# Dario_-_Rev_A1.net
KiCad netlist of a schematic drawn in EAGLE
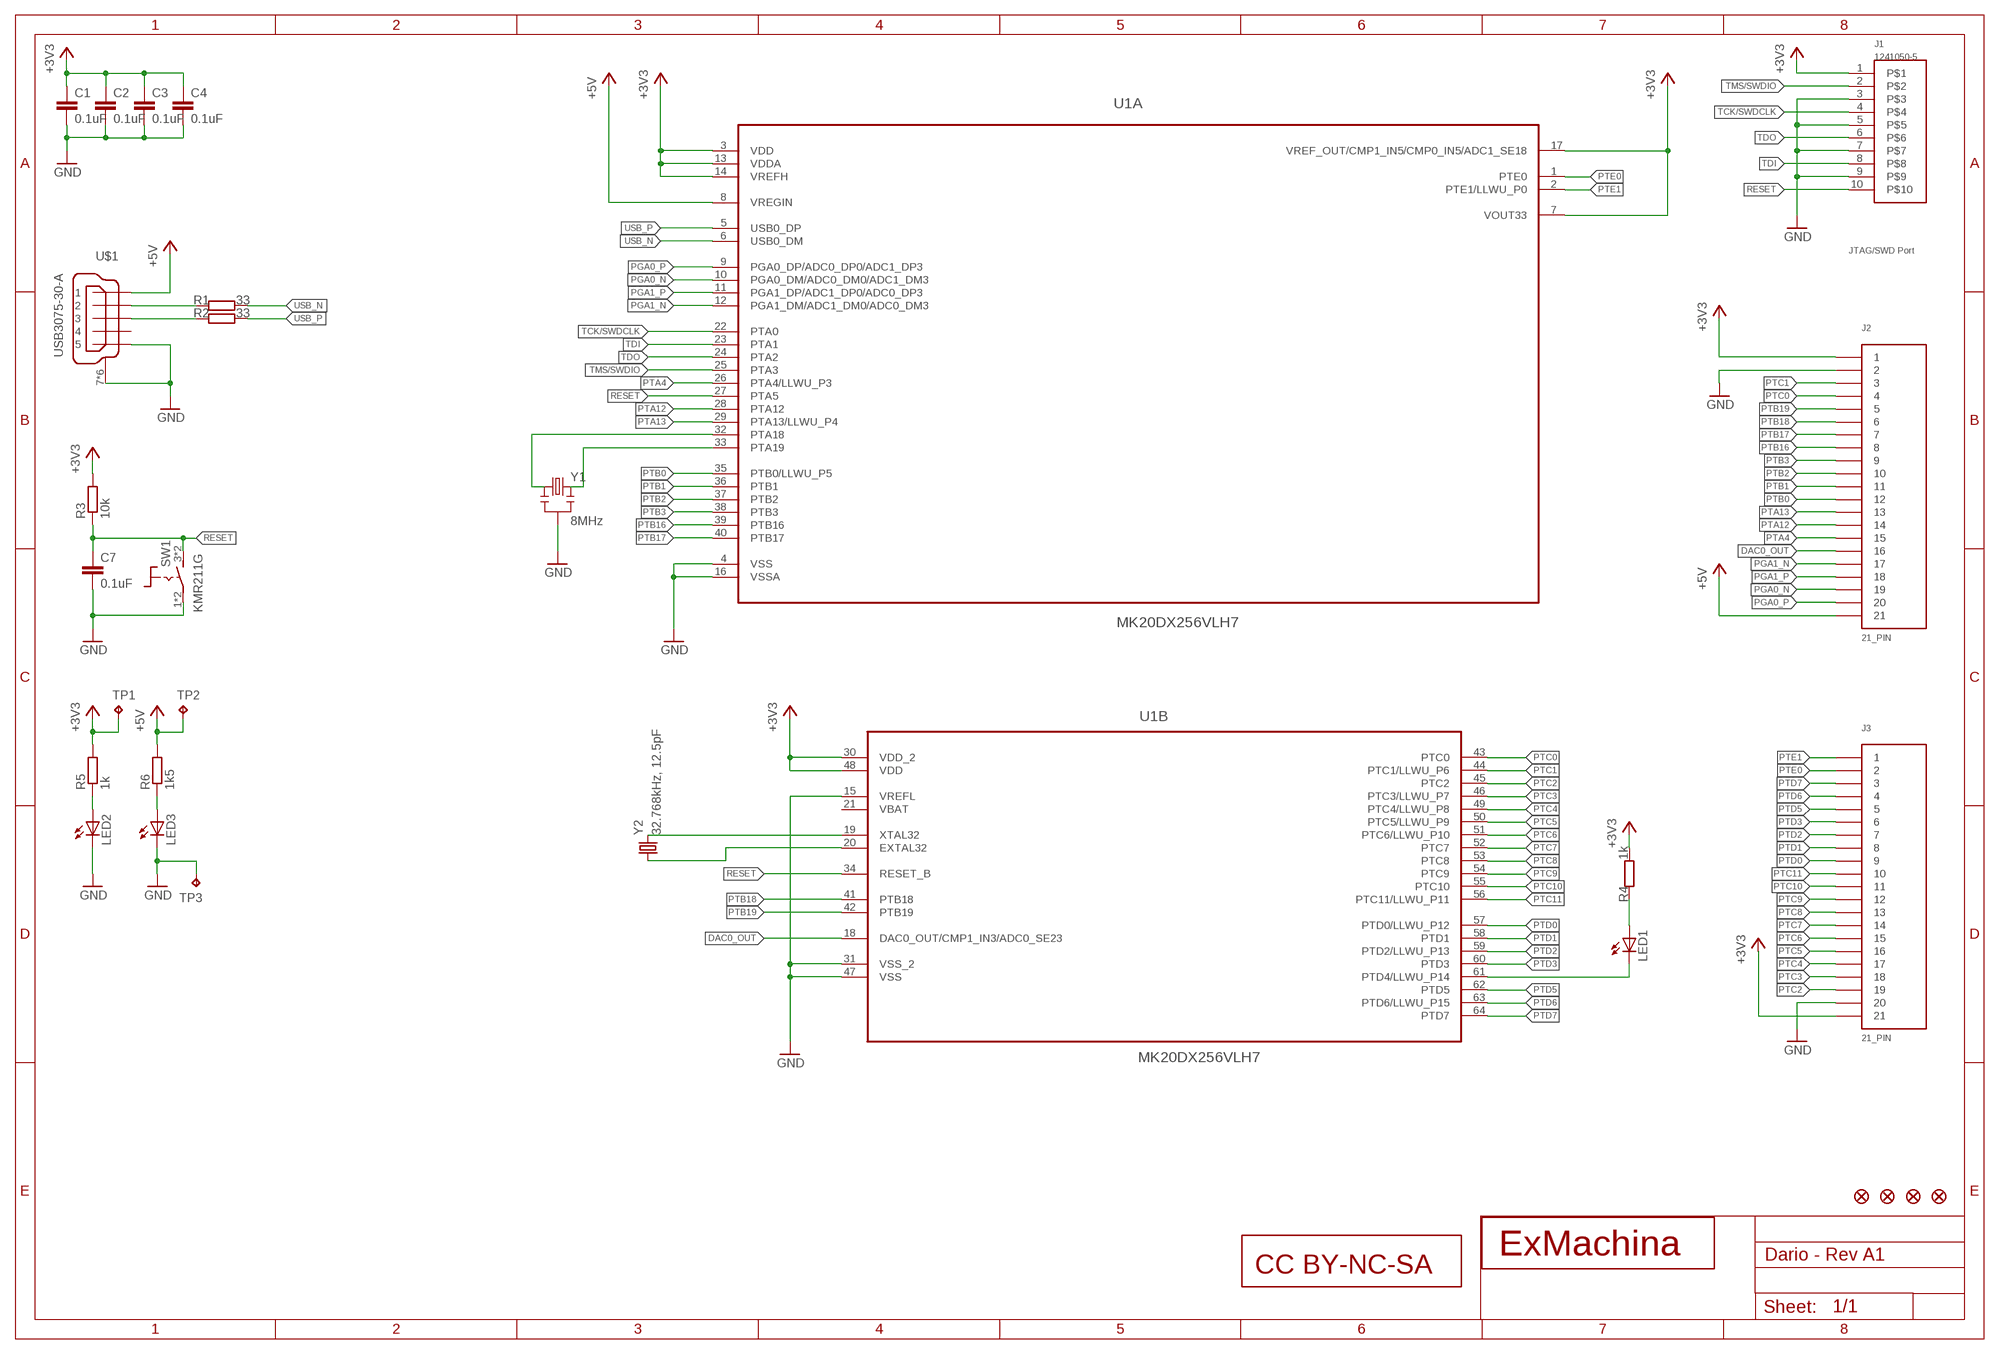
[diagram p0: schematic, sheet 1]

(export (version "E")
  (design (tool "Eeschema 10.0.6"))
  (components
    (comp (ref "C1")
      (value "0.1uF")
      (footprint "eagle-import:C0603")
      (fields (field (name "MPN") "MC0603B104K160CT"))
      (libsource (lib "eagle-import") (part "C-EUC0603"))
    )
    (comp (ref "C2")
      (value "0.1uF")
      (footprint "eagle-import:C0603")
      (fields (field (name "MPN") "MC0603B104K160CT"))
      (libsource (lib "eagle-import") (part "C-EUC0603"))
    )
    (comp (ref "C3")
      (value "0.1uF")
      (footprint "eagle-import:C0603")
      (fields (field (name "MPN") "MC0603B104K160CT"))
      (libsource (lib "eagle-import") (part "C-EUC0603"))
    )
    (comp (ref "C4")
      (value "0.1uF")
      (footprint "eagle-import:C0603")
      (fields (field (name "MPN") "MC0603B104K160CT"))
      (libsource (lib "eagle-import") (part "C-EUC0603"))
    )
    (comp (ref "C7")
      (value "0.1uF")
      (footprint "eagle-import:C0603")
      (fields (field (name "MPN") "MC0603B104K160CT"))
      (libsource (lib "eagle-import") (part "C-EUC0603"))
    )
    (comp (ref "J1")
      (value "1241050-5")
      (footprint "eagle-import:2.54_2X5")
      (libsource (lib "eagle-import") (part "1241050-5"))
    )
    (comp (ref "J2")
      (value "21_PIN")
      (footprint "eagle-import:21_CUSTOM")
      (libsource (lib "eagle-import") (part "21_PIN"))
    )
    (comp (ref "J3")
      (value "21_PIN")
      (footprint "eagle-import:21_CUSTOM")
      (libsource (lib "eagle-import") (part "21_PIN"))
    )
    (comp (ref "JP1")
      (value "FIDUCIAL1X2")
      (footprint "eagle-import:FIDUCIAL-1X2")
      (libsource (lib "eagle-import") (part "FIDUCIAL1X2"))
    )
    (comp (ref "JP2")
      (value "FIDUCIAL1X2")
      (footprint "eagle-import:FIDUCIAL-1X2")
      (libsource (lib "eagle-import") (part "FIDUCIAL1X2"))
    )
    (comp (ref "JP3")
      (value "FIDUCIAL1X2")
      (footprint "eagle-import:FIDUCIAL-1X2")
      (libsource (lib "eagle-import") (part "FIDUCIAL1X2"))
    )
    (comp (ref "JP4")
      (value "FIDUCIAL1X2")
      (footprint "eagle-import:FIDUCIAL-1X2")
      (libsource (lib "eagle-import") (part "FIDUCIAL1X2"))
    )
    (comp (ref "LED1")
      (value "LEDCHIP-LED0603")
      (footprint "eagle-import:CHIP-LED0603")
      (libsource (lib "eagle-import") (part "LEDCHIP-LED0603"))
    )
    (comp (ref "LED2")
      (value "LEDCHIP-LED0603")
      (footprint "eagle-import:CHIP-LED0603")
      (libsource (lib "eagle-import") (part "LEDCHIP-LED0603"))
    )
    (comp (ref "LED3")
      (value "LEDCHIP-LED0603")
      (footprint "eagle-import:CHIP-LED0603")
      (libsource (lib "eagle-import") (part "LEDCHIP-LED0603"))
    )
    (comp (ref "R1")
      (value "33")
      (footprint "eagle-import:R0603")
      (fields (field (name "MPN") "MCMR06X33R0FTL"))
      (libsource (lib "eagle-import") (part "R-EU_R0603"))
    )
    (comp (ref "R2")
      (value "33")
      (footprint "eagle-import:R0603")
      (fields (field (name "MPN") "MCMR06X33R0FTL"))
      (libsource (lib "eagle-import") (part "R-EU_R0603"))
    )
    (comp (ref "R3")
      (value "10k")
      (footprint "eagle-import:R0603")
      (fields (field (name "MPN") "MCMR06X1002FTL"))
      (libsource (lib "eagle-import") (part "R-EU_R0603"))
    )
    (comp (ref "R4")
      (value "1k")
      (footprint "eagle-import:R0603")
      (fields (field (name "MPN") "MCMR06X1001FTL"))
      (libsource (lib "eagle-import") (part "R-EU_R0603"))
    )
    (comp (ref "R5")
      (value "1k")
      (footprint "eagle-import:R0603")
      (fields (field (name "MPN") "MCMR06X1001FTL"))
      (libsource (lib "eagle-import") (part "R-EU_R0603"))
    )
    (comp (ref "R6")
      (value "1k5")
      (footprint "eagle-import:R0603")
      (fields (field (name "MPN") "MCMR06X1501FTL"))
      (libsource (lib "eagle-import") (part "R-EU_R0603"))
    )
    (comp (ref "SW1")
      (value "KMR211G")
      (footprint "eagle-import:KM_SERIE")
      (fields (field (name "MPN") "KMR211G LFS"))
      (libsource (lib "eagle-import") (part "KMR211G"))
    )
    (comp (ref "TP1")
      (value "TPB1,27")
      (footprint "eagle-import:B1,27")
      (libsource (lib "eagle-import") (part "TPB1,27"))
    )
    (comp (ref "TP2")
      (value "TPB1,27")
      (footprint "eagle-import:B1,27")
      (libsource (lib "eagle-import") (part "TPB1,27"))
    )
    (comp (ref "TP3")
      (value "TPB1,27")
      (footprint "eagle-import:B1,27")
      (libsource (lib "eagle-import") (part "TPB1,27"))
    )
    (comp (ref "U$1")
      (value "USB3075-30-A")
      (footprint "eagle-import:USB_MICROB_SMT")
      (libsource (lib "eagle-import") (part "USB3075-30-A"))
    )
    (comp (ref "U$3")
      (value "EXMACHINA-LOGO-NAME")
      (footprint "eagle-import:EXM-LOGO-BASELINE")
      (libsource (lib "eagle-import") (part "EXMACHINA-LOGO-NAME"))
    )
    (comp (ref "U$4")
      (value "CC-BY-NC-SA")
      (footprint "eagle-import:CC-BY-NC-SA")
      (libsource (lib "eagle-import") (part "CC-BY-NC-SA"))
    )
    (comp (ref "U1")
      (value "MK20DX256VLH7")
      (footprint "eagle-import:QFP50P1200X1200X160-64N")
      (libsource (lib "eagle-import") (part "MK20DX256VLH7"))
    )
    (comp (ref "Y1")
      (value "8MHz")
      (footprint "eagle-import:RESONATOR-SMD")
      (fields (field (name "MPN") "CSTCE8M00G55Z-R0"))
      (libsource (lib "eagle-import") (part "RESONATORSMD"))
    )
    (comp (ref "Y2")
      (value "32.768kHz, 12.5pF")
      (footprint "eagle-import:ABS07")
      (fields (field (name "MPN") "ABS07-32.768KHZ-1-T"))
      (libsource (lib "eagle-import") (part "ABS07-?32.768KHZ"))
    )
  )
  (nets
    (net (code "1") (name "+3V3") (class "Default")
      (node (ref "C1") (pin "1") (pinfunction "1_1") (pintype "passive"))
      (node (ref "C2") (pin "1") (pinfunction "1_1") (pintype "passive"))
      (node (ref "C3") (pin "1") (pinfunction "1_1") (pintype "passive"))
      (node (ref "C4") (pin "1") (pinfunction "1_1") (pintype "passive"))
      (node (ref "J1") (pin "1") (pinfunction "P$1_1") (pintype "bidirectional"))
      (node (ref "J2") (pin "P$1") (pinfunction "1_P$1") (pintype "bidirectional"))
      (node (ref "J3") (pin "P$21") (pinfunction "21_P$21") (pintype "bidirectional"))
      (node (ref "R3") (pin "2") (pinfunction "2_2") (pintype "passive"))
      (node (ref "R4") (pin "2") (pinfunction "2_2") (pintype "passive"))
      (node (ref "R5") (pin "2") (pinfunction "2_2") (pintype "passive"))
      (node (ref "TP1") (pin "TP") (pinfunction "TP_TP") (pintype "input"))
      (node (ref "U1") (pin "13") (pinfunction "VDDA_13") (pintype "power_in"))
      (node (ref "U1") (pin "14") (pinfunction "VREFH_14") (pintype "passive"))
      (node (ref "U1") (pin "17") (pinfunction "VREF_OUT/CMP1_IN5/CMP0_IN5/ADC1_SE18_17") (pintype "output"))
      (node (ref "U1") (pin "3") (pinfunction "VDD_3") (pintype "power_in"))
      (node (ref "U1") (pin "30") (pinfunction "VDD_2_30") (pintype "power_in"))
      (node (ref "U1") (pin "48") (pinfunction "VDD_48") (pintype "power_in"))
      (node (ref "U1") (pin "7") (pinfunction "VOUT33_7") (pintype "output"))
    )
    (net (code "2") (name "+5V") (class "Default")
      (node (ref "J2") (pin "P$21") (pinfunction "21_P$21") (pintype "bidirectional"))
      (node (ref "R6") (pin "2") (pinfunction "2_2") (pintype "passive"))
      (node (ref "TP2") (pin "TP") (pinfunction "TP_TP") (pintype "input"))
      (node (ref "U$1") (pin "1") (pinfunction "1_1") (pintype "passive"))
      (node (ref "U1") (pin "8") (pinfunction "VREGIN_8") (pintype "input"))
    )
    (net (code "3") (name "/VBAT") (class "Default")
      (node (ref "U1") (pin "21") (pinfunction "VBAT_21") (pintype "power_in"))
    )
    (net (code "4") (name "DAC0_OUT") (class "Default")
      (node (ref "J2") (pin "P$16") (pinfunction "16_P$16") (pintype "bidirectional"))
      (node (ref "U1") (pin "18") (pinfunction "DAC0_OUT/CMP1_IN3/ADC0_SE23_18") (pintype "passive"))
    )
    (net (code "5") (name "GND") (class "Default")
      (node (ref "C1") (pin "2") (pinfunction "2_2") (pintype "passive"))
      (node (ref "C2") (pin "2") (pinfunction "2_2") (pintype "passive"))
      (node (ref "C3") (pin "2") (pinfunction "2_2") (pintype "passive"))
      (node (ref "C4") (pin "2") (pinfunction "2_2") (pintype "passive"))
      (node (ref "C7") (pin "2") (pinfunction "2_2") (pintype "passive"))
      (node (ref "J1") (pin "3") (pinfunction "P$3_3") (pintype "bidirectional"))
      (node (ref "J1") (pin "5") (pinfunction "P$5_5") (pintype "bidirectional"))
      (node (ref "J1") (pin "7") (pinfunction "P$7_7") (pintype "bidirectional"))
      (node (ref "J1") (pin "9") (pinfunction "P$9_9") (pintype "bidirectional"))
      (node (ref "J2") (pin "P$2") (pinfunction "2_P$2") (pintype "bidirectional"))
      (node (ref "J3") (pin "P$20") (pinfunction "20_P$20") (pintype "bidirectional"))
      (node (ref "LED2") (pin "C") (pinfunction "C_C") (pintype "passive"))
      (node (ref "LED3") (pin "C") (pinfunction "C_C") (pintype "passive"))
      (node (ref "SW1") (pin "1") (pinfunction "2_1") (pintype "passive"))
      (node (ref "SW1") (pin "2") (pinfunction "2_2") (pintype "passive"))
      (node (ref "TP3") (pin "TP") (pinfunction "TP_TP") (pintype "input"))
      (node (ref "U$1") (pin "10") (pinfunction "S_10") (pintype "bidirectional"))
      (node (ref "U$1") (pin "11") (pinfunction "S_11") (pintype "bidirectional"))
      (node (ref "U$1") (pin "12") (pinfunction "S_12") (pintype "bidirectional"))
      (node (ref "U$1") (pin "5") (pinfunction "5_5") (pintype "passive"))
      (node (ref "U$1") (pin "7") (pinfunction "S_7") (pintype "bidirectional"))
      (node (ref "U$1") (pin "8") (pinfunction "S_8") (pintype "bidirectional"))
      (node (ref "U$1") (pin "9") (pinfunction "S_9") (pintype "bidirectional"))
      (node (ref "U1") (pin "15") (pinfunction "VREFL_15") (pintype "passive"))
      (node (ref "U1") (pin "16") (pinfunction "VSSA_16") (pintype "passive"))
      (node (ref "U1") (pin "31") (pinfunction "VSS_2_31") (pintype "passive"))
      (node (ref "U1") (pin "4") (pinfunction "VSS_4") (pintype "passive"))
      (node (ref "U1") (pin "47") (pinfunction "VSS_47") (pintype "passive"))
      (node (ref "Y1") (pin "2") (pinfunction "2_2") (pintype "passive"))
    )
    (net (code "6") (name "Net-(LED1-PadA)") (class "Default")
      (node (ref "LED1") (pin "A") (pinfunction "A_A") (pintype "passive"))
      (node (ref "R4") (pin "1") (pinfunction "1_1") (pintype "passive"))
    )
    (net (code "7") (name "Net-(LED2-PadA)") (class "Default")
      (node (ref "LED2") (pin "A") (pinfunction "A_A") (pintype "passive"))
      (node (ref "R5") (pin "1") (pinfunction "1_1") (pintype "passive"))
    )
    (net (code "8") (name "Net-(LED3-PadA)") (class "Default")
      (node (ref "LED3") (pin "A") (pinfunction "A_A") (pintype "passive"))
      (node (ref "R6") (pin "1") (pinfunction "1_1") (pintype "passive"))
    )
    (net (code "9") (name "Net-(R1-Pad1)") (class "Default")
      (node (ref "R1") (pin "1") (pinfunction "1_1") (pintype "passive"))
      (node (ref "U$1") (pin "2") (pinfunction "2_2") (pintype "passive"))
    )
    (net (code "10") (name "Net-(R2-Pad1)") (class "Default")
      (node (ref "R2") (pin "1") (pinfunction "1_1") (pintype "passive"))
      (node (ref "U$1") (pin "3") (pinfunction "3_3") (pintype "passive"))
    )
    (net (code "11") (name "Net-(U1A-PTA18)") (class "Default")
      (node (ref "U1") (pin "32") (pinfunction "PTA18_32") (pintype "bidirectional"))
      (node (ref "Y1") (pin "1") (pinfunction "1_1") (pintype "passive"))
    )
    (net (code "12") (name "Net-(U1A-PTA19)") (class "Default")
      (node (ref "U1") (pin "33") (pinfunction "PTA19_33") (pintype "bidirectional"))
      (node (ref "Y1") (pin "3") (pinfunction "3_3") (pintype "passive"))
    )
    (net (code "13") (name "Net-(U1B-EXTAL32)") (class "Default")
      (node (ref "U1") (pin "20") (pinfunction "EXTAL32_20") (pintype "passive"))
      (node (ref "Y2") (pin "1") (pinfunction "1_1") (pintype "passive"))
    )
    (net (code "14") (name "Net-(U1B-PTD4{slash}LLWU_P14)") (class "Default")
      (node (ref "LED1") (pin "C") (pinfunction "C_C") (pintype "passive"))
      (node (ref "U1") (pin "61") (pinfunction "PTD4/LLWU_P14_61") (pintype "bidirectional"))
    )
    (net (code "15") (name "Net-(U1B-XTAL32)") (class "Default")
      (node (ref "U1") (pin "19") (pinfunction "XTAL32_19") (pintype "passive"))
      (node (ref "Y2") (pin "2") (pinfunction "2_2") (pintype "passive"))
    )
    (net (code "16") (name "PGA0_N") (class "Default")
      (node (ref "J2") (pin "P$19") (pinfunction "19_P$19") (pintype "bidirectional"))
      (node (ref "U1") (pin "10") (pinfunction "PGA0_DM/ADC0_DM0/ADC1_DM3_10") (pintype "bidirectional"))
    )
    (net (code "17") (name "PGA0_P") (class "Default")
      (node (ref "J2") (pin "P$20") (pinfunction "20_P$20") (pintype "bidirectional"))
      (node (ref "U1") (pin "9") (pinfunction "PGA0_DP/ADC0_DP0/ADC1_DP3_9") (pintype "bidirectional"))
    )
    (net (code "18") (name "PGA1_N") (class "Default")
      (node (ref "J2") (pin "P$17") (pinfunction "17_P$17") (pintype "bidirectional"))
      (node (ref "U1") (pin "12") (pinfunction "PGA1_DM/ADC1_DM0/ADC0_DM3_12") (pintype "bidirectional"))
    )
    (net (code "19") (name "PGA1_P") (class "Default")
      (node (ref "J2") (pin "P$18") (pinfunction "18_P$18") (pintype "bidirectional"))
      (node (ref "U1") (pin "11") (pinfunction "PGA1_DP/ADC1_DP0/ADC0_DP3_11") (pintype "bidirectional"))
    )
    (net (code "20") (name "PTA4") (class "Default")
      (node (ref "J2") (pin "P$15") (pinfunction "15_P$15") (pintype "bidirectional"))
      (node (ref "U1") (pin "26") (pinfunction "PTA4/LLWU_P3_26") (pintype "bidirectional"))
    )
    (net (code "21") (name "PTA12") (class "Default")
      (node (ref "J2") (pin "P$14") (pinfunction "14_P$14") (pintype "bidirectional"))
      (node (ref "U1") (pin "28") (pinfunction "PTA12_28") (pintype "bidirectional"))
    )
    (net (code "22") (name "PTA13") (class "Default")
      (node (ref "J2") (pin "P$13") (pinfunction "13_P$13") (pintype "bidirectional"))
      (node (ref "U1") (pin "29") (pinfunction "PTA13/LLWU_P4_29") (pintype "bidirectional"))
    )
    (net (code "23") (name "PTB0") (class "Default")
      (node (ref "J2") (pin "P$12") (pinfunction "12_P$12") (pintype "bidirectional"))
      (node (ref "U1") (pin "35") (pinfunction "PTB0/LLWU_P5_35") (pintype "bidirectional"))
    )
    (net (code "24") (name "PTB1") (class "Default")
      (node (ref "J2") (pin "P$11") (pinfunction "11_P$11") (pintype "bidirectional"))
      (node (ref "U1") (pin "36") (pinfunction "PTB1_36") (pintype "bidirectional"))
    )
    (net (code "25") (name "PTB2") (class "Default")
      (node (ref "J2") (pin "P$10") (pinfunction "10_P$10") (pintype "bidirectional"))
      (node (ref "U1") (pin "37") (pinfunction "PTB2_37") (pintype "bidirectional"))
    )
    (net (code "26") (name "PTB3") (class "Default")
      (node (ref "J2") (pin "P$9") (pinfunction "9_P$9") (pintype "bidirectional"))
      (node (ref "U1") (pin "38") (pinfunction "PTB3_38") (pintype "bidirectional"))
    )
    (net (code "27") (name "PTB16") (class "Default")
      (node (ref "J2") (pin "P$8") (pinfunction "8_P$8") (pintype "bidirectional"))
      (node (ref "U1") (pin "39") (pinfunction "PTB16_39") (pintype "bidirectional"))
    )
    (net (code "28") (name "PTB17") (class "Default")
      (node (ref "J2") (pin "P$7") (pinfunction "7_P$7") (pintype "bidirectional"))
      (node (ref "U1") (pin "40") (pinfunction "PTB17_40") (pintype "bidirectional"))
    )
    (net (code "29") (name "PTB18") (class "Default")
      (node (ref "J2") (pin "P$6") (pinfunction "6_P$6") (pintype "bidirectional"))
      (node (ref "U1") (pin "41") (pinfunction "PTB18_41") (pintype "bidirectional"))
    )
    (net (code "30") (name "PTB19") (class "Default")
      (node (ref "J2") (pin "P$5") (pinfunction "5_P$5") (pintype "bidirectional"))
      (node (ref "U1") (pin "42") (pinfunction "PTB19_42") (pintype "bidirectional"))
    )
    (net (code "31") (name "PTC0") (class "Default")
      (node (ref "J2") (pin "P$4") (pinfunction "4_P$4") (pintype "bidirectional"))
      (node (ref "U1") (pin "43") (pinfunction "PTC0_43") (pintype "bidirectional"))
    )
    (net (code "32") (name "PTC1") (class "Default")
      (node (ref "J2") (pin "P$3") (pinfunction "3_P$3") (pintype "bidirectional"))
      (node (ref "U1") (pin "44") (pinfunction "PTC1/LLWU_P6_44") (pintype "bidirectional"))
    )
    (net (code "33") (name "PTC2") (class "Default")
      (node (ref "J3") (pin "P$19") (pinfunction "19_P$19") (pintype "bidirectional"))
      (node (ref "U1") (pin "45") (pinfunction "PTC2_45") (pintype "bidirectional"))
    )
    (net (code "34") (name "PTC3") (class "Default")
      (node (ref "J3") (pin "P$18") (pinfunction "18_P$18") (pintype "bidirectional"))
      (node (ref "U1") (pin "46") (pinfunction "PTC3/LLWU_P7_46") (pintype "bidirectional"))
    )
    (net (code "35") (name "PTC4") (class "Default")
      (node (ref "J3") (pin "P$17") (pinfunction "17_P$17") (pintype "bidirectional"))
      (node (ref "U1") (pin "49") (pinfunction "PTC4/LLWU_P8_49") (pintype "bidirectional"))
    )
    (net (code "36") (name "PTC5") (class "Default")
      (node (ref "J3") (pin "P$16") (pinfunction "16_P$16") (pintype "bidirectional"))
      (node (ref "U1") (pin "50") (pinfunction "PTC5/LLWU_P9_50") (pintype "bidirectional"))
    )
    (net (code "37") (name "PTC6") (class "Default")
      (node (ref "J3") (pin "P$15") (pinfunction "15_P$15") (pintype "bidirectional"))
      (node (ref "U1") (pin "51") (pinfunction "PTC6/LLWU_P10_51") (pintype "bidirectional"))
    )
    (net (code "38") (name "PTC7") (class "Default")
      (node (ref "J3") (pin "P$14") (pinfunction "14_P$14") (pintype "bidirectional"))
      (node (ref "U1") (pin "52") (pinfunction "PTC7_52") (pintype "bidirectional"))
    )
    (net (code "39") (name "PTC8") (class "Default")
      (node (ref "J3") (pin "P$13") (pinfunction "13_P$13") (pintype "bidirectional"))
      (node (ref "U1") (pin "53") (pinfunction "PTC8_53") (pintype "bidirectional"))
    )
    (net (code "40") (name "PTC9") (class "Default")
      (node (ref "J3") (pin "P$12") (pinfunction "12_P$12") (pintype "bidirectional"))
      (node (ref "U1") (pin "54") (pinfunction "PTC9_54") (pintype "bidirectional"))
    )
    (net (code "41") (name "PTC10") (class "Default")
      (node (ref "J3") (pin "P$11") (pinfunction "11_P$11") (pintype "bidirectional"))
      (node (ref "U1") (pin "55") (pinfunction "PTC10_55") (pintype "bidirectional"))
    )
    (net (code "42") (name "PTC11") (class "Default")
      (node (ref "J3") (pin "P$10") (pinfunction "10_P$10") (pintype "bidirectional"))
      (node (ref "U1") (pin "56") (pinfunction "PTC11/LLWU_P11_56") (pintype "bidirectional"))
    )
    (net (code "43") (name "PTD0") (class "Default")
      (node (ref "J3") (pin "P$9") (pinfunction "9_P$9") (pintype "bidirectional"))
      (node (ref "U1") (pin "57") (pinfunction "PTD0/LLWU_P12_57") (pintype "bidirectional"))
    )
    (net (code "44") (name "PTD1") (class "Default")
      (node (ref "J3") (pin "P$8") (pinfunction "8_P$8") (pintype "bidirectional"))
      (node (ref "U1") (pin "58") (pinfunction "PTD1_58") (pintype "bidirectional"))
    )
    (net (code "45") (name "PTD2") (class "Default")
      (node (ref "J3") (pin "P$7") (pinfunction "7_P$7") (pintype "bidirectional"))
      (node (ref "U1") (pin "59") (pinfunction "PTD2/LLWU_P13_59") (pintype "bidirectional"))
    )
    (net (code "46") (name "PTD3") (class "Default")
      (node (ref "J3") (pin "P$6") (pinfunction "6_P$6") (pintype "bidirectional"))
      (node (ref "U1") (pin "60") (pinfunction "PTD3_60") (pintype "bidirectional"))
    )
    (net (code "47") (name "PTD5") (class "Default")
      (node (ref "J3") (pin "P$5") (pinfunction "5_P$5") (pintype "bidirectional"))
      (node (ref "U1") (pin "62") (pinfunction "PTD5_62") (pintype "bidirectional"))
    )
    (net (code "48") (name "PTD6") (class "Default")
      (node (ref "J3") (pin "P$4") (pinfunction "4_P$4") (pintype "bidirectional"))
      (node (ref "U1") (pin "63") (pinfunction "PTD6/LLWU_P15_63") (pintype "bidirectional"))
    )
    (net (code "49") (name "PTD7") (class "Default")
      (node (ref "J3") (pin "P$3") (pinfunction "3_P$3") (pintype "bidirectional"))
      (node (ref "U1") (pin "64") (pinfunction "PTD7_64") (pintype "bidirectional"))
    )
    (net (code "50") (name "PTE0") (class "Default")
      (node (ref "J3") (pin "P$2") (pinfunction "2_P$2") (pintype "bidirectional"))
      (node (ref "U1") (pin "1") (pinfunction "PTE0_1") (pintype "bidirectional"))
    )
    (net (code "51") (name "PTE1") (class "Default")
      (node (ref "J3") (pin "P$1") (pinfunction "1_P$1") (pintype "bidirectional"))
      (node (ref "U1") (pin "2") (pinfunction "PTE1/LLWU_P0_2") (pintype "bidirectional"))
    )
    (net (code "52") (name "RESET") (class "Default")
      (node (ref "C7") (pin "1") (pinfunction "1_1") (pintype "passive"))
      (node (ref "J1") (pin "10") (pinfunction "P$10_10") (pintype "bidirectional"))
      (node (ref "R3") (pin "1") (pinfunction "1_1") (pintype "passive"))
      (node (ref "SW1") (pin "3") (pinfunction "1_3") (pintype "passive"))
      (node (ref "SW1") (pin "4") (pinfunction "1_4") (pintype "passive"))
      (node (ref "U1") (pin "27") (pinfunction "PTA5_27") (pintype "bidirectional"))
      (node (ref "U1") (pin "34") (pinfunction "RESET_B_34") (pintype "passive"))
    )
    (net (code "53") (name "TCK{slash}SWDCLK") (class "Default")
      (node (ref "J1") (pin "4") (pinfunction "P$4_4") (pintype "bidirectional"))
      (node (ref "U1") (pin "22") (pinfunction "PTA0_22") (pintype "bidirectional"))
    )
    (net (code "54") (name "TDI") (class "Default")
      (node (ref "J1") (pin "8") (pinfunction "P$8_8") (pintype "bidirectional"))
      (node (ref "U1") (pin "23") (pinfunction "PTA1_23") (pintype "bidirectional"))
    )
    (net (code "55") (name "TDO") (class "Default")
      (node (ref "J1") (pin "6") (pinfunction "P$6_6") (pintype "bidirectional"))
      (node (ref "U1") (pin "24") (pinfunction "PTA2_24") (pintype "bidirectional"))
    )
    (net (code "56") (name "TMS{slash}SWDIO") (class "Default")
      (node (ref "J1") (pin "2") (pinfunction "P$2_2") (pintype "bidirectional"))
      (node (ref "U1") (pin "25") (pinfunction "PTA3_25") (pintype "bidirectional"))
    )
    (net (code "57") (name "USB_N") (class "Default")
      (node (ref "R1") (pin "2") (pinfunction "2_2") (pintype "passive"))
      (node (ref "U1") (pin "6") (pinfunction "USB0_DM_6") (pintype "passive"))
    )
    (net (code "58") (name "USB_P") (class "Default")
      (node (ref "R2") (pin "2") (pinfunction "2_2") (pintype "passive"))
      (node (ref "U1") (pin "5") (pinfunction "USB0_DP_5") (pintype "passive"))
    )
    (net (code "59") (name "unconnected-(U$1-Pad4)") (class "Default")
      (node (ref "U$1") (pin "4") (pinfunction "4_4") (pintype "passive"))
    )
  )
)
